# Mixer.net
KiCad netlist of a schematic drawn in Altium Designer
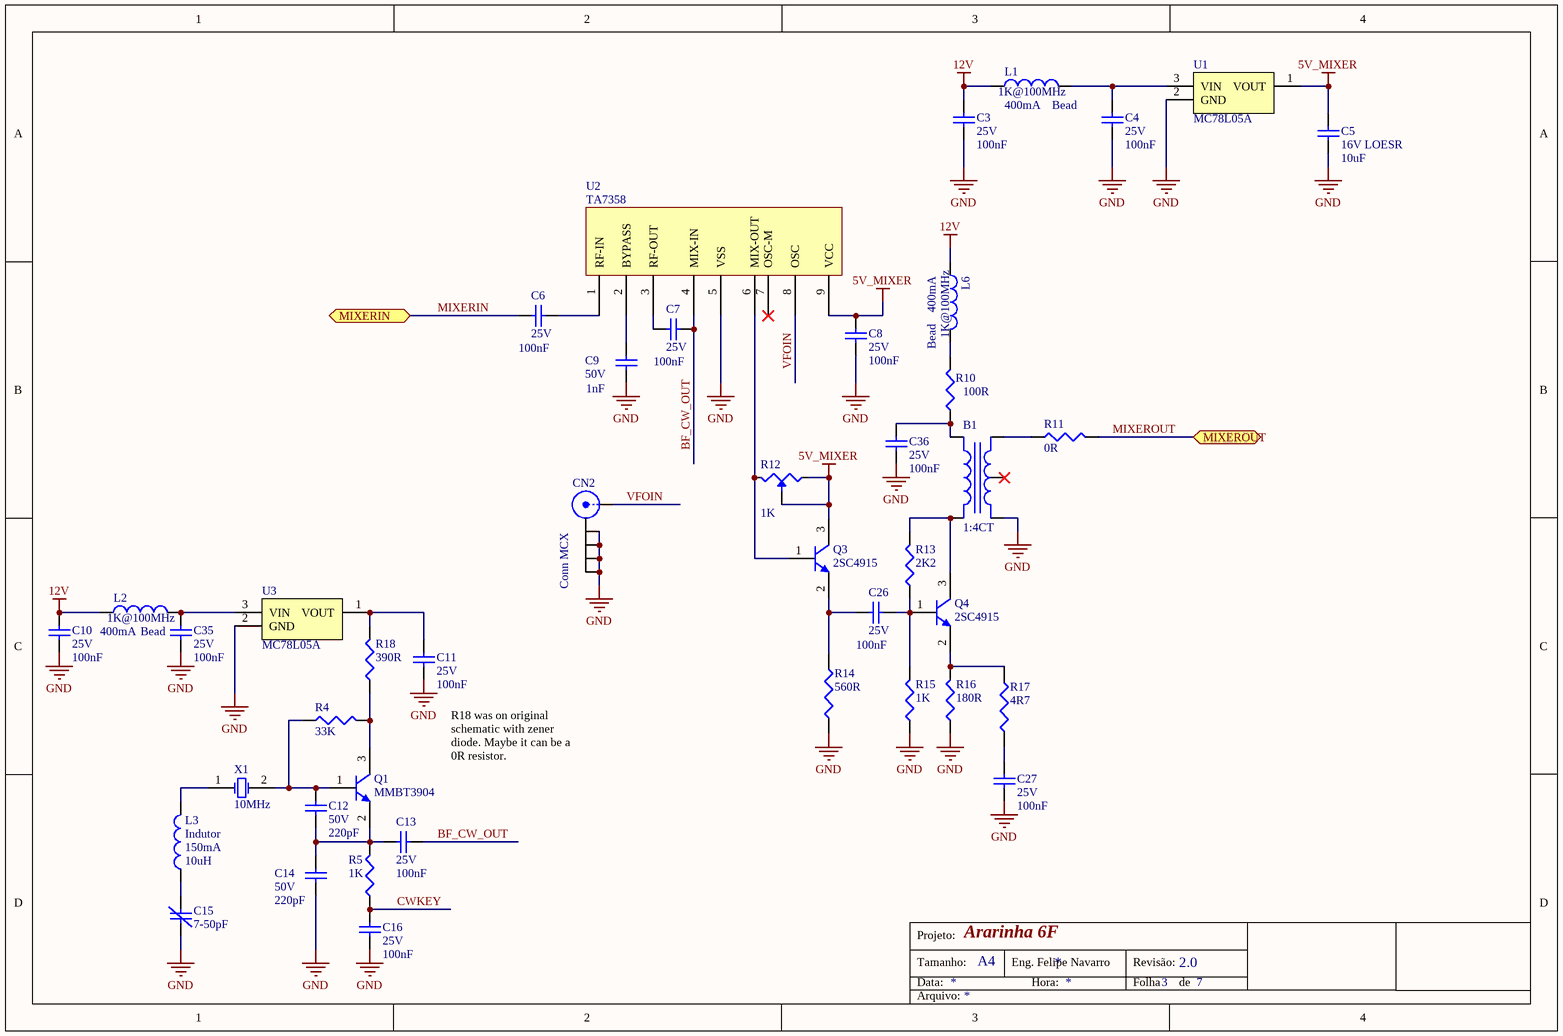
[diagram p0: Mixer.SchDoc]

(export (version "E")
  (design (tool "Eeschema 10.0.6"))
  (components
    (comp (ref "B1")
      (value "1:4CT")
      (footprint "CX2047LANL")
      (description "Balun 4CT:1")
      (libsource (lib "NavarroIND") (part "BALUN CX2047LANL"))
    )
    (comp (ref "C3")
      (value "100nF")
      (footprint "CC0603")
      (description "Capacitor (Semiconductor SIM Model)")
      (fields (field (name "TENSÃO") "25V") (field (name "Comment") "Capacitor Cerâmico"))
      (libsource (lib "NavarroCAP") (part "Cap 100nF 25V 0603 X7R"))
    )
    (comp (ref "C4")
      (value "100nF")
      (footprint "CC0603")
      (description "Capacitor (Semiconductor SIM Model)")
      (fields (field (name "TENSÃO") "25V") (field (name "Comment") "Capacitor Cerâmico"))
      (libsource (lib "NavarroCAP") (part "Cap 100nF 25V 0603 X7R"))
    )
    (comp (ref "C5")
      (value "10uF")
      (footprint "CC0805")
      (description "Capacitor (Semiconductor SIM Model)")
      (fields (field (name "TENSÃO") "16V LOESR") (field (name "Comment") "Capacitor Cerâmico"))
      (libsource (lib "NavarroCAP") (part "Cap 10uF 16V 0805 X6S LOESR"))
    )
    (comp (ref "C6")
      (value "100nF")
      (footprint "CC0603")
      (description "Capacitor (Semiconductor SIM Model)")
      (fields (field (name "TENSÃO") "25V") (field (name "Comment") "Capacitor Cerâmico"))
      (libsource (lib "NavarroCAP") (part "Cap 100nF 25V 0603 X7R"))
    )
    (comp (ref "C7")
      (value "100nF")
      (footprint "CC0603")
      (description "Capacitor (Semiconductor SIM Model)")
      (fields (field (name "TENSÃO") "25V") (field (name "Comment") "Capacitor Cerâmico"))
      (libsource (lib "NavarroCAP") (part "Cap 100nF 25V 0603 X7R"))
    )
    (comp (ref "C8")
      (value "100nF")
      (footprint "CC0603")
      (description "Capacitor (Semiconductor SIM Model)")
      (fields (field (name "TENSÃO") "25V") (field (name "Comment") "Capacitor Cerâmico"))
      (libsource (lib "NavarroCAP") (part "Cap 100nF 25V 0603 X7R"))
    )
    (comp (ref "C9")
      (value "1nF")
      (footprint "CC0603")
      (description "Capacitor (Semiconductor SIM Model)")
      (fields (field (name "TENSÃO") "50V") (field (name "Comment") "Capacitor Cerâmico"))
      (libsource (lib "NavarroCAP") (part "Cap 1nF 50V 0603 NP0"))
    )
    (comp (ref "C10")
      (value "100nF")
      (footprint "CC0603")
      (description "Capacitor (Semiconductor SIM Model)")
      (fields (field (name "TENSÃO") "25V") (field (name "Comment") "Capacitor Cerâmico"))
      (libsource (lib "NavarroCAP") (part "Cap 100nF 25V 0603 X7R"))
    )
    (comp (ref "C11")
      (value "100nF")
      (footprint "CC0603")
      (description "Capacitor (Semiconductor SIM Model)")
      (fields (field (name "TENSÃO") "25V") (field (name "Comment") "Capacitor Cerâmico"))
      (libsource (lib "NavarroCAP") (part "Cap 100nF 25V 0603 X7R"))
    )
    (comp (ref "C12")
      (value "220pF")
      (footprint "CC0603")
      (description "Capacitor (Semiconductor SIM Model)")
      (fields (field (name "TENSÃO") "50V") (field (name "Comment") "Capacitor Cerâmico"))
      (libsource (lib "NavarroCAP") (part "Cap 220pF 50V 0603 NP0"))
    )
    (comp (ref "C13")
      (value "100nF")
      (footprint "CC0603")
      (description "Capacitor (Semiconductor SIM Model)")
      (fields (field (name "TENSÃO") "25V") (field (name "Comment") "Capacitor Cerâmico"))
      (libsource (lib "NavarroCAP") (part "Cap 2.2pf 50V 0603 C0G"))
    )
    (comp (ref "C14")
      (value "220pF")
      (footprint "CC0603")
      (description "Capacitor (Semiconductor SIM Model)")
      (fields (field (name "TENSÃO") "50V") (field (name "Comment") "Capacitor Cerâmico"))
      (libsource (lib "NavarroCAP") (part "Cap 220pF 50V 0603 NP0"))
    )
    (comp (ref "C15")
      (value "7-50pF")
      (footprint "MURATA TZB4")
      (description "Capacitor (Semiconductor SIM Model)")
      (fields (field (name "Comment") "Trimmer"))
      (libsource (lib "NavarroCAP") (part "Trimmer 7-50pF 50V TZB4-BB"))
    )
    (comp (ref "C16")
      (value "100nF")
      (footprint "CC0603")
      (description "Capacitor (Semiconductor SIM Model)")
      (fields (field (name "TENSÃO") "25V") (field (name "Comment") "Capacitor Cerâmico"))
      (libsource (lib "NavarroCAP") (part "Cap 100nF 25V 0603 X7R"))
    )
    (comp (ref "C26")
      (value "100nF")
      (footprint "CC0603")
      (description "Capacitor (Semiconductor SIM Model)")
      (fields (field (name "TENSÃO") "25V") (field (name "Comment") "Capacitor Cerâmico"))
      (libsource (lib "NavarroCAP") (part "Cap 100nF 25V 0603 X7R"))
    )
    (comp (ref "C27")
      (value "100nF")
      (footprint "CC0603")
      (description "Capacitor (Semiconductor SIM Model)")
      (fields (field (name "TENSÃO") "25V") (field (name "Comment") "Capacitor Cerâmico"))
      (libsource (lib "NavarroCAP") (part "Cap 100nF 25V 0603 X7R"))
    )
    (comp (ref "C35")
      (value "100nF")
      (footprint "CC0603")
      (description "Capacitor (Semiconductor SIM Model)")
      (fields (field (name "TENSÃO") "25V") (field (name "Comment") "Capacitor Cerâmico"))
      (libsource (lib "NavarroCAP") (part "Cap 100nF 25V 0603 X7R"))
    )
    (comp (ref "C36")
      (value "100nF")
      (footprint "CC0603")
      (description "Capacitor (Semiconductor SIM Model)")
      (fields (field (name "TENSÃO") "25V") (field (name "Comment") "Capacitor Cerâmico"))
      (libsource (lib "NavarroCAP") (part "Cap 100nF 25V 0603 X7R"))
    )
    (comp (ref "CN2")
      (value "Conn MCX")
      (footprint "CONN MCX MOLEX")
      (description "Conector MCX")
      (libsource (lib "NavarroCON") (part "Conn MCX"))
    )
    (comp (ref "L1")
      (value "Bead")
      (footprint "CC0603")
      (fields (field (name "CORRENTE") "400mA") (field (name "ALTIUM_VALUE") "1K@100MHz"))
      (libsource (lib "NavarroIND") (part "Bd 1K@100MHz 0603 400mA"))
    )
    (comp (ref "L2")
      (value "Bead")
      (footprint "CC0603")
      (fields (field (name "CORRENTE") "400mA") (field (name "ALTIUM_VALUE") "1K@100MHz"))
      (libsource (lib "NavarroIND") (part "Bd 1K@100MHz 0603 400mA"))
    )
    (comp (ref "L3")
      (value "Indutor")
      (footprint "CC0805")
      (description "Inductor")
      (fields (field (name "CORRENTE") "150mA") (field (name "ALTIUM_VALUE") "10uH"))
      (libsource (lib "NavarroIND") (part "Ind 10uH 0805 150mA"))
    )
    (comp (ref "L6")
      (value "Bead")
      (footprint "CC0603")
      (fields (field (name "CORRENTE") "400mA") (field (name "ALTIUM_VALUE") "1K@100MHz"))
      (libsource (lib "NavarroIND") (part "Bd 1K@100MHz 0603 400mA"))
    )
    (comp (ref "Q1")
      (value "MMBT3904")
      (footprint "SOT-23-3N")
      (description "NPN General Purpose Amplifier")
      (libsource (lib "NavarroSEMI") (part "TRS MMBT2222 40V 200mA SOT-23-3N"))
    )
    (comp (ref "Q3")
      (value "2SC4915")
      (footprint "SOT-23-3N")
      (description "NPN General Purpose Amplifier")
      (libsource (lib "NavarroSEMI") (part "TRS 2SC3324 120V 100mA SOT-23-3"))
    )
    (comp (ref "Q4")
      (value "2SC4915")
      (footprint "SOT-23-3N")
      (description "NPN General Purpose Amplifier")
      (libsource (lib "NavarroSEMI") (part "TRS 2SC3324 120V 100mA SOT-23-3"))
    )
    (comp (ref "R4")
      (value "33K")
      (footprint "CC0603")
      (description "Resistor")
      (libsource (lib "NavarroRES") (part "Res 33K 1% 0603 1/10W"))
    )
    (comp (ref "R5")
      (value "1K")
      (footprint "CC0603")
      (description "Resistor")
      (libsource (lib "NavarroRES") (part "Res 1K 1% 0603 1/10W"))
    )
    (comp (ref "R10")
      (value "100R")
      (footprint "CC0805")
      (description "Resistor")
      (libsource (lib "NavarroRES") (part "Res 100R 5% 0805 1/8W"))
    )
    (comp (ref "R11")
      (value "0R")
      (footprint "CC0603~0805")
      (description "Resistor")
      (libsource (lib "NavarroRES") (part "Res 0R 0603 1/10W"))
    )
    (comp (ref "R12")
      (value "1K")
      (footprint "POT")
      (description "Potenciometro")
      (fields (field (name "Comment") "Potenciômetro"))
      (libsource (lib "NavarroRES") (part "Res Pot"))
    )
    (comp (ref "R13")
      (value "2K2")
      (footprint "CC0603")
      (description "Resistor")
      (libsource (lib "NavarroRES") (part "Res 2K2 5% 0603 1/10W"))
    )
    (comp (ref "R14")
      (value "560R")
      (footprint "CC0603")
      (description "Resistor")
      (libsource (lib "NavarroRES") (part "Res 560R 1% 0603 1/10w"))
    )
    (comp (ref "R15")
      (value "1K")
      (footprint "CC0603")
      (description "Resistor")
      (libsource (lib "NavarroRES") (part "Res 1K 1% 0603 1/10W"))
    )
    (comp (ref "R16")
      (value "180R")
      (footprint "CC0603")
      (description "Resistor")
      (libsource (lib "NavarroRES") (part "Res 180R 1% 0603 1/10W"))
    )
    (comp (ref "R17")
      (value "4R7")
      (footprint "CC0603")
      (description "Resistor")
      (libsource (lib "NavarroRES") (part "Res 4R7 1% 0603 1/10W"))
    )
    (comp (ref "R18")
      (value "390R")
      (footprint "CC0603")
      (description "Resistor")
      (libsource (lib "NavarroRES") (part "Res 390R 1% 0603 1/10W"))
    )
    (comp (ref "U1")
      (value "MC78L05A")
      (footprint "SOT-89-3N")
      (description "Regulador Linear 5V")
      (libsource (lib "Navarro") (part "MC78L05"))
    )
    (comp (ref "U2")
      (value "TA7358")
      (footprint "SIP9")
      (description "FM FRONT-END")
      (libsource (lib "Navarro") (part "TA7358"))
    )
    (comp (ref "U3")
      (value "MC78L05A")
      (footprint "SOT-89-3N")
      (description "Regulador Linear 5V")
      (libsource (lib "Navarro") (part "MC78L05"))
    )
    (comp (ref "X1")
      (value "10MHz")
      (footprint "HC/49US")
      (description "Crystal Oscillator")
      (libsource (lib "Navarro") (part "XTAL"))
    )
  )
  (nets
    (net (code "1") (name "/BF_CW_OUT") (class "Default")
      (node (ref "C13") (pin "2") (pinfunction "2_2") (pintype "passive"))
      (node (ref "C7") (pin "1") (pinfunction "1_1") (pintype "passive"))
      (node (ref "U2") (pin "4") (pinfunction "MIX-IN_4") (pintype "passive"))
    )
    (net (code "2") (name "/CWKEY") (class "Default")
      (node (ref "C16") (pin "2") (pinfunction "2_2") (pintype "passive"))
      (node (ref "R5") (pin "1") (pinfunction "1_1") (pintype "passive"))
    )
    (net (code "3") (name "/MIXERIN") (class "Default")
      (node (ref "C6") (pin "2") (pinfunction "2_2") (pintype "passive"))
    )
    (net (code "4") (name "/MIXEROUT") (class "Default")
      (node (ref "R11") (pin "2") (pinfunction "2_2") (pintype "passive"))
    )
    (net (code "5") (name "/VFOIN") (class "Default")
      (node (ref "CN2") (pin "1") (pinfunction "X_1") (pintype "passive"))
      (node (ref "U2") (pin "8") (pinfunction "OSC_8") (pintype "passive"))
    )
    (net (code "6") (name "5V_MIXER") (class "Default")
      (node (ref "C5") (pin "2") (pinfunction "2_2") (pintype "passive"))
      (node (ref "C8") (pin "1") (pinfunction "1_1") (pintype "passive"))
      (node (ref "Q3") (pin "3") (pinfunction "C_3") (pintype "passive"))
      (node (ref "R12") (pin "1") (pinfunction "1_1") (pintype "passive"))
      (node (ref "R12") (pin "2") (pinfunction "TAP_2") (pintype "passive"))
      (node (ref "U1") (pin "1") (pinfunction "VOUT_1") (pintype "power_in"))
      (node (ref "U2") (pin "9") (pinfunction "VCC_9") (pintype "passive"))
    )
    (net (code "7") (name "12V") (class "Default")
      (node (ref "C10") (pin "2") (pinfunction "2_2") (pintype "passive"))
      (node (ref "C3") (pin "1") (pinfunction "1_1") (pintype "passive"))
      (node (ref "L1") (pin "1") (pinfunction "1_1") (pintype "passive"))
      (node (ref "L2") (pin "1") (pinfunction "1_1") (pintype "passive"))
      (node (ref "L6") (pin "1") (pinfunction "1_1") (pintype "passive"))
    )
    (net (code "8") (name "GND") (class "Default")
      (node (ref "B1") (pin "3") (pinfunction "Pri-_3") (pintype "passive"))
      (node (ref "C10") (pin "1") (pinfunction "1_1") (pintype "passive"))
      (node (ref "C11") (pin "1") (pinfunction "1_1") (pintype "passive"))
      (node (ref "C14") (pin "1") (pinfunction "1_1") (pintype "passive"))
      (node (ref "C15") (pin "1") (pinfunction "1_1") (pintype "passive"))
      (node (ref "C16") (pin "1") (pinfunction "1_1") (pintype "passive"))
      (node (ref "C27") (pin "2") (pinfunction "2_2") (pintype "passive"))
      (node (ref "C3") (pin "2") (pinfunction "2_2") (pintype "passive"))
      (node (ref "C35") (pin "1") (pinfunction "1_1") (pintype "passive"))
      (node (ref "C36") (pin "2") (pinfunction "2_2") (pintype "passive"))
      (node (ref "C4") (pin "2") (pinfunction "2_2") (pintype "passive"))
      (node (ref "C5") (pin "1") (pinfunction "1_1") (pintype "passive"))
      (node (ref "C8") (pin "2") (pinfunction "2_2") (pintype "passive"))
      (node (ref "C9") (pin "2") (pinfunction "2_2") (pintype "passive"))
      (node (ref "CN2") (pin "2") (pinfunction "Y_2") (pintype "passive"))
      (node (ref "CN2") (pin "3") (pinfunction "Y_3") (pintype "passive"))
      (node (ref "CN2") (pin "4") (pinfunction "Y_4") (pintype "passive"))
      (node (ref "CN2") (pin "5") (pinfunction "Y_5") (pintype "passive"))
      (node (ref "R14") (pin "1") (pinfunction "1_1") (pintype "passive"))
      (node (ref "R15") (pin "1") (pinfunction "1_1") (pintype "passive"))
      (node (ref "R16") (pin "1") (pinfunction "1_1") (pintype "passive"))
      (node (ref "U1") (pin "2") (pinfunction "GND_2") (pintype "power_in"))
      (node (ref "U2") (pin "5") (pinfunction "VSS_5") (pintype "passive"))
      (node (ref "U3") (pin "2") (pinfunction "GND_2") (pintype "power_in"))
    )
    (net (code "9") (name "Net-(B1-Pri+)") (class "Default")
      (node (ref "B1") (pin "4") (pinfunction "Pri+_4") (pintype "passive"))
      (node (ref "Q4") (pin "3") (pinfunction "C_3") (pintype "passive"))
      (node (ref "R13") (pin "2") (pinfunction "2_2") (pintype "passive"))
    )
    (net (code "10") (name "Net-(B1-Sec+-Pad1)") (class "Default")
      (node (ref "B1") (pin "1") (pinfunction "Sec+_1") (pintype "passive"))
      (node (ref "R11") (pin "1") (pinfunction "1_1") (pintype "passive"))
    )
    (net (code "11") (name "Net-(B1-Sec-)") (class "Default")
      (node (ref "B1") (pin "6") (pinfunction "Sec-_6") (pintype "passive"))
      (node (ref "C36") (pin "1") (pinfunction "1_1") (pintype "passive"))
      (node (ref "R10") (pin "1") (pinfunction "1_1") (pintype "passive"))
    )
    (net (code "12") (name "Net-(C15-Pad2)") (class "Default")
      (node (ref "C15") (pin "2") (pinfunction "2_2") (pintype "passive"))
      (node (ref "L3") (pin "1") (pinfunction "1_1") (pintype "passive"))
    )
    (net (code "13") (name "Net-(C27-Pad1)") (class "Default")
      (node (ref "C27") (pin "1") (pinfunction "1_1") (pintype "passive"))
      (node (ref "R17") (pin "1") (pinfunction "1_1") (pintype "passive"))
    )
    (net (code "14") (name "Net-(L6-Pad2)") (class "Default")
      (node (ref "L6") (pin "2") (pinfunction "2_2") (pintype "passive"))
      (node (ref "R10") (pin "2") (pinfunction "2_2") (pintype "passive"))
    )
    (net (code "15") (name "Net-(Q1-B)") (class "Default")
      (node (ref "C12") (pin "2") (pinfunction "2_2") (pintype "passive"))
      (node (ref "Q1") (pin "1") (pinfunction "B_1") (pintype "passive"))
      (node (ref "R4") (pin "1") (pinfunction "1_1") (pintype "passive"))
      (node (ref "X1") (pin "2") (pinfunction "OSC2_2") (pintype "passive"))
    )
    (net (code "16") (name "Net-(Q1-C)") (class "Default")
      (node (ref "Q1") (pin "3") (pinfunction "C_3") (pintype "passive"))
      (node (ref "R18") (pin "1") (pinfunction "1_1") (pintype "passive"))
      (node (ref "R4") (pin "2") (pinfunction "2_2") (pintype "passive"))
    )
    (net (code "17") (name "Net-(Q1-E)") (class "Default")
      (node (ref "C12") (pin "1") (pinfunction "1_1") (pintype "passive"))
      (node (ref "C13") (pin "1") (pinfunction "1_1") (pintype "passive"))
      (node (ref "C14") (pin "2") (pinfunction "2_2") (pintype "passive"))
      (node (ref "Q1") (pin "2") (pinfunction "E_2") (pintype "passive"))
      (node (ref "R5") (pin "2") (pinfunction "2_2") (pintype "passive"))
    )
    (net (code "18") (name "Net-(Q3-B)") (class "Default")
      (node (ref "Q3") (pin "1") (pinfunction "B_1") (pintype "passive"))
      (node (ref "R12") (pin "3") (pinfunction "3_3") (pintype "passive"))
      (node (ref "U2") (pin "6") (pinfunction "MIX-OUT_6") (pintype "passive"))
    )
    (net (code "19") (name "Net-(Q3-E)") (class "Default")
      (node (ref "C26") (pin "2") (pinfunction "2_2") (pintype "passive"))
      (node (ref "Q3") (pin "2") (pinfunction "E_2") (pintype "passive"))
      (node (ref "R14") (pin "2") (pinfunction "2_2") (pintype "passive"))
    )
    (net (code "20") (name "Net-(Q4-B)") (class "Default")
      (node (ref "C26") (pin "1") (pinfunction "1_1") (pintype "passive"))
      (node (ref "Q4") (pin "1") (pinfunction "B_1") (pintype "passive"))
      (node (ref "R13") (pin "1") (pinfunction "1_1") (pintype "passive"))
      (node (ref "R15") (pin "2") (pinfunction "2_2") (pintype "passive"))
    )
    (net (code "21") (name "Net-(Q4-E)") (class "Default")
      (node (ref "Q4") (pin "2") (pinfunction "E_2") (pintype "passive"))
      (node (ref "R16") (pin "2") (pinfunction "2_2") (pintype "passive"))
      (node (ref "R17") (pin "2") (pinfunction "2_2") (pintype "passive"))
    )
    (net (code "22") (name "Net-(U1-VIN)") (class "Default")
      (node (ref "C4") (pin "1") (pinfunction "1_1") (pintype "passive"))
      (node (ref "L1") (pin "2") (pinfunction "2_2") (pintype "passive"))
      (node (ref "U1") (pin "3") (pinfunction "VIN_3") (pintype "power_in"))
    )
    (net (code "23") (name "Net-(U2-BYPASS)") (class "Default")
      (node (ref "C9") (pin "1") (pinfunction "1_1") (pintype "passive"))
      (node (ref "U2") (pin "2") (pinfunction "BYPASS_2") (pintype "passive"))
    )
    (net (code "24") (name "Net-(U2-RF-IN)") (class "Default")
      (node (ref "C6") (pin "1") (pinfunction "1_1") (pintype "passive"))
      (node (ref "U2") (pin "1") (pinfunction "RF-IN_1") (pintype "passive"))
    )
    (net (code "25") (name "Net-(U2-RF-OUT)") (class "Default")
      (node (ref "C7") (pin "2") (pinfunction "2_2") (pintype "passive"))
      (node (ref "U2") (pin "3") (pinfunction "RF-OUT_3") (pintype "passive"))
    )
    (net (code "26") (name "Net-(U3-VIN)") (class "Default")
      (node (ref "C35") (pin "2") (pinfunction "2_2") (pintype "passive"))
      (node (ref "L2") (pin "2") (pinfunction "2_2") (pintype "passive"))
      (node (ref "U3") (pin "3") (pinfunction "VIN_3") (pintype "power_in"))
    )
    (net (code "27") (name "Net-(U3-VOUT)") (class "Default")
      (node (ref "C11") (pin "2") (pinfunction "2_2") (pintype "passive"))
      (node (ref "R18") (pin "2") (pinfunction "2_2") (pintype "passive"))
      (node (ref "U3") (pin "1") (pinfunction "VOUT_1") (pintype "power_in"))
    )
    (net (code "28") (name "Net-(X1-OSC1)") (class "Default")
      (node (ref "L3") (pin "2") (pinfunction "2_2") (pintype "passive"))
      (node (ref "X1") (pin "1") (pinfunction "OSC1_1") (pintype "passive"))
    )
    (net (code "29") (name "unconnected-(B1-Sec+-Pad2)") (class "Default")
      (node (ref "B1") (pin "2") (pinfunction "Sec+_2") (pintype "passive+no_connect"))
    )
    (net (code "30") (name "unconnected-(U2-OSC-M-Pad7)") (class "Default")
      (node (ref "U2") (pin "7") (pinfunction "OSC-M_7") (pintype "passive+no_connect"))
    )
  )
)
